# Main_Board.net
KiCad netlist of a schematic drawn in EAGLE
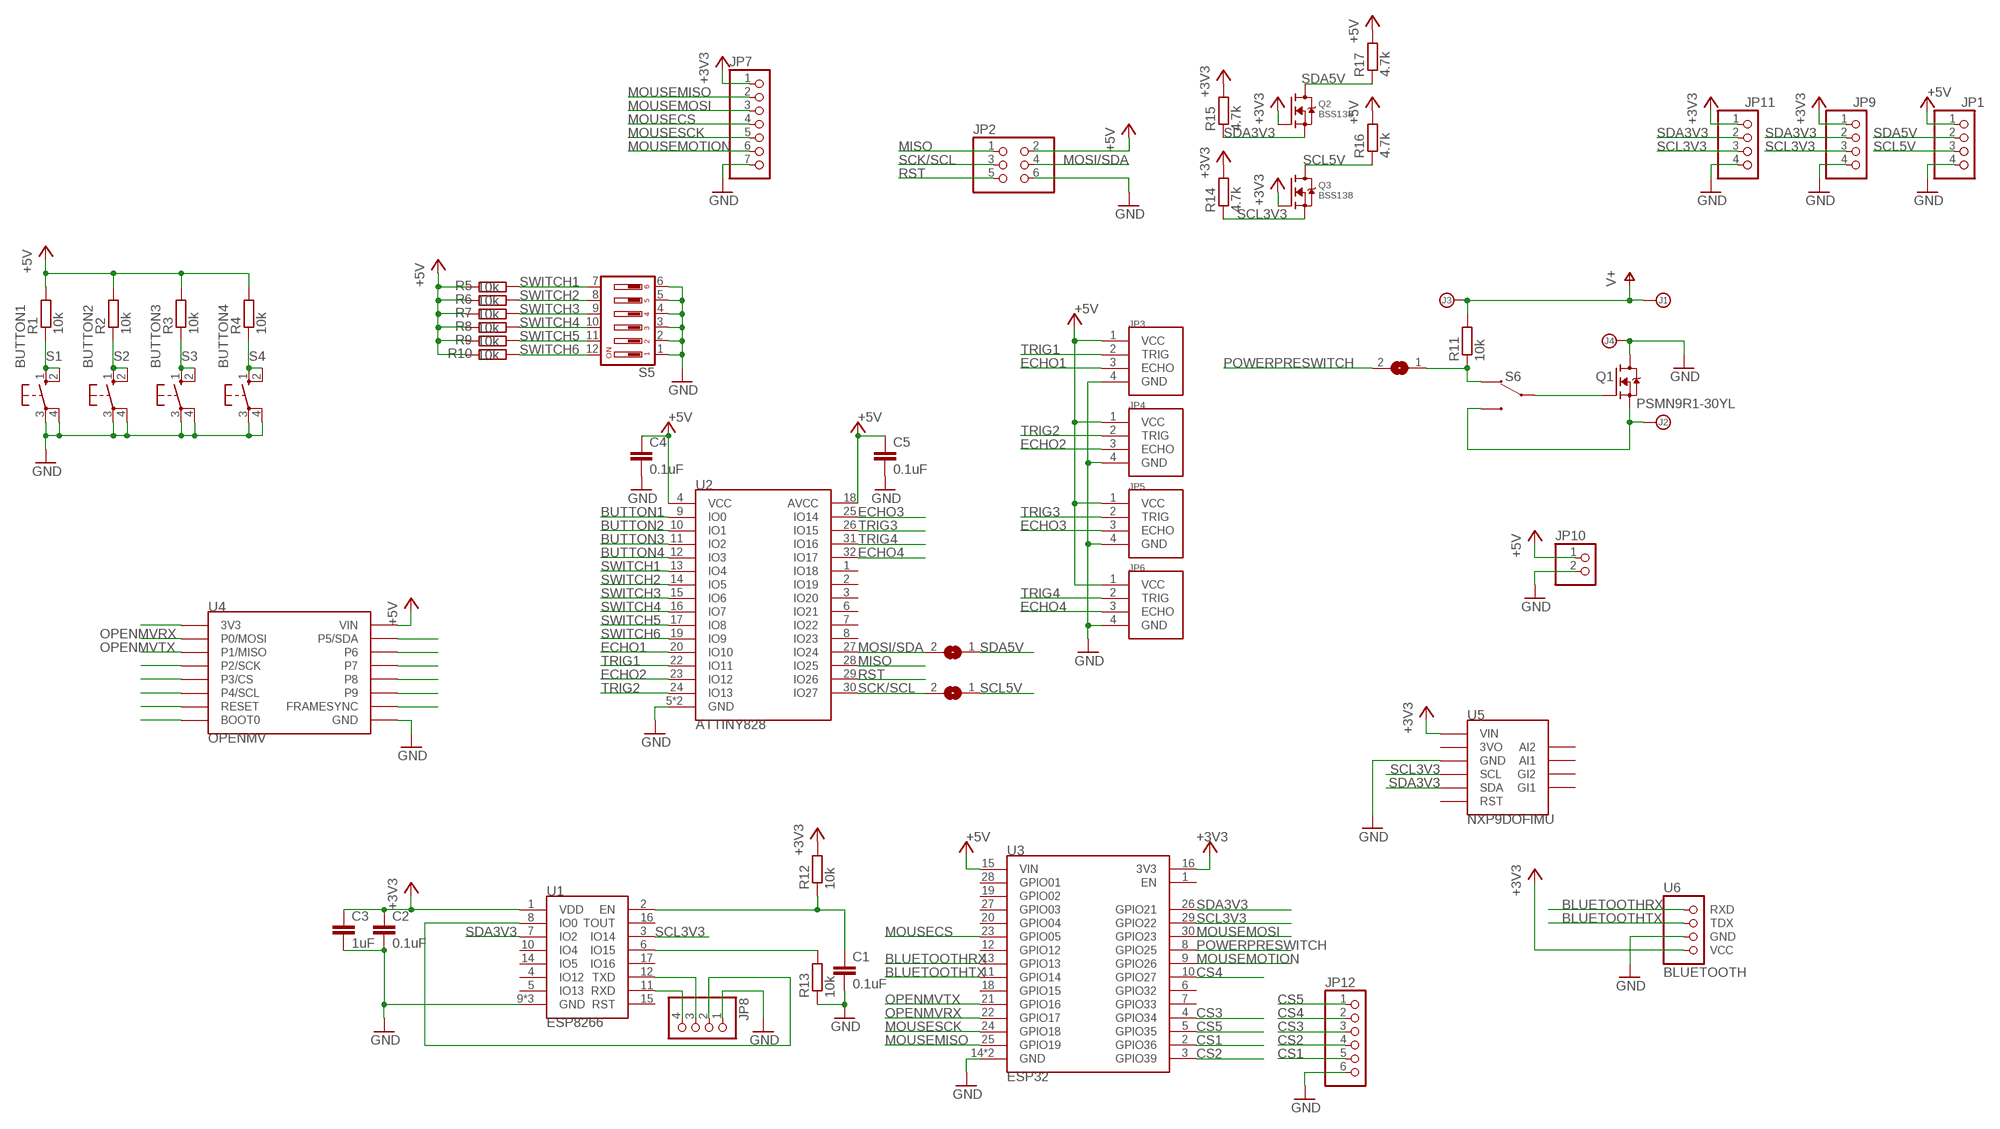
[diagram p0: schematic, sheet 1]

(export (version "E")
  (design (tool "Eeschema 10.0.6"))
  (components
    (comp (ref "C1")
      (value "0.1uF")
      (footprint "eagle-import:C0805")
      (libsource (lib "eagle-import") (part "C-EUC0805"))
    )
    (comp (ref "C2")
      (value "0.1uF")
      (footprint "eagle-import:C0805")
      (libsource (lib "eagle-import") (part "C-EUC0805"))
    )
    (comp (ref "C3")
      (value "1uF")
      (footprint "eagle-import:C0805")
      (libsource (lib "eagle-import") (part "C-EUC0805"))
    )
    (comp (ref "C4")
      (value "0.1uF")
      (footprint "eagle-import:C0805")
      (libsource (lib "eagle-import") (part "C-EUC0805"))
    )
    (comp (ref "C5")
      (value "0.1uF")
      (footprint "eagle-import:C0805")
      (libsource (lib "eagle-import") (part "C-EUC0805"))
    )
    (comp (ref "J1")
      (value "MOLEXQUICKCONNECT")
      (footprint "eagle-import:MOLEXQUICKCONNECT")
      (libsource (lib "eagle-import") (part "MOLEXQUICKCONNECT"))
    )
    (comp (ref "J2")
      (value "MOLEXQUICKCONNECT")
      (footprint "eagle-import:MOLEXQUICKCONNECT")
      (libsource (lib "eagle-import") (part "MOLEXQUICKCONNECT"))
    )
    (comp (ref "J3")
      (value "MOLEXQUICKCONNECT")
      (footprint "eagle-import:MOLEXQUICKCONNECT")
      (libsource (lib "eagle-import") (part "MOLEXQUICKCONNECT"))
    )
    (comp (ref "J4")
      (value "MOLEXQUICKCONNECT")
      (footprint "eagle-import:MOLEXQUICKCONNECT")
      (libsource (lib "eagle-import") (part "MOLEXQUICKCONNECT"))
    )
    (comp (ref "JP1")
      (value "PINHD-1X4")
      (footprint "eagle-import:1X04")
      (libsource (lib "eagle-import") (part "PINHD-1X4"))
    )
    (comp (ref "JP2")
      (value "PINHD-2X3")
      (footprint "eagle-import:2X03")
      (libsource (lib "eagle-import") (part "PINHD-2X3"))
    )
    (comp (ref "JP3")
      (value "HC-SR04")
      (footprint "eagle-import:HC-SR04")
      (libsource (lib "eagle-import") (part "HC-SR04"))
    )
    (comp (ref "JP4")
      (value "HC-SR04")
      (footprint "eagle-import:HC-SR04")
      (libsource (lib "eagle-import") (part "HC-SR04"))
    )
    (comp (ref "JP5")
      (value "HC-SR04")
      (footprint "eagle-import:HC-SR04")
      (libsource (lib "eagle-import") (part "HC-SR04"))
    )
    (comp (ref "JP6")
      (value "HC-SR04")
      (footprint "eagle-import:HC-SR04")
      (libsource (lib "eagle-import") (part "HC-SR04"))
    )
    (comp (ref "JP7")
      (value "PINHD-1X7")
      (footprint "eagle-import:1X07")
      (libsource (lib "eagle-import") (part "PINHD-1X7"))
    )
    (comp (ref "JP8")
      (value "PINHD-1X4")
      (footprint "eagle-import:1X04")
      (libsource (lib "eagle-import") (part "PINHD-1X4"))
    )
    (comp (ref "JP9")
      (value "PINHD-1X4")
      (footprint "eagle-import:1X04")
      (libsource (lib "eagle-import") (part "PINHD-1X4"))
    )
    (comp (ref "JP10")
      (value "PINHD-1X2")
      (footprint "eagle-import:1X02")
      (libsource (lib "eagle-import") (part "PINHD-1X2"))
    )
    (comp (ref "JP11")
      (value "PINHD-1X4")
      (footprint "eagle-import:1X04")
      (libsource (lib "eagle-import") (part "PINHD-1X4"))
    )
    (comp (ref "JP12")
      (value "PINHD-1X6")
      (footprint "eagle-import:1X06")
      (libsource (lib "eagle-import") (part "PINHD-1X6"))
    )
    (comp (ref "Q1")
      (value "PSMN9R1-30YL")
      (footprint "eagle-import:LFPAK")
      (libsource (lib "eagle-import") (part "PSMN9R1-30YL"))
    )
    (comp (ref "Q2")
      (value "BSS138")
      (footprint "eagle-import:SOT95P240X120-3N")
      (fields (field (name "RS_PART_NUMBER") "1241694"))
      (libsource (lib "eagle-import") (part "BSS138"))
    )
    (comp (ref "Q3")
      (value "BSS138")
      (footprint "eagle-import:SOT95P240X120-3N")
      (fields (field (name "RS_PART_NUMBER") "1241694"))
      (libsource (lib "eagle-import") (part "BSS138"))
    )
    (comp (ref "R1")
      (value "10k")
      (footprint "eagle-import:R0805")
      (libsource (lib "eagle-import") (part "R-EU_R0805"))
    )
    (comp (ref "R2")
      (value "10k")
      (footprint "eagle-import:R0805")
      (libsource (lib "eagle-import") (part "R-EU_R0805"))
    )
    (comp (ref "R3")
      (value "10k")
      (footprint "eagle-import:R0805")
      (libsource (lib "eagle-import") (part "R-EU_R0805"))
    )
    (comp (ref "R4")
      (value "10k")
      (footprint "eagle-import:R0805")
      (libsource (lib "eagle-import") (part "R-EU_R0805"))
    )
    (comp (ref "R5")
      (value "10k")
      (footprint "eagle-import:R0805")
      (libsource (lib "eagle-import") (part "R-EU_R0805"))
    )
    (comp (ref "R6")
      (value "10k")
      (footprint "eagle-import:R0805")
      (libsource (lib "eagle-import") (part "R-EU_R0805"))
    )
    (comp (ref "R7")
      (value "10k")
      (footprint "eagle-import:R0805")
      (libsource (lib "eagle-import") (part "R-EU_R0805"))
    )
    (comp (ref "R8")
      (value "10k")
      (footprint "eagle-import:R0805")
      (libsource (lib "eagle-import") (part "R-EU_R0805"))
    )
    (comp (ref "R9")
      (value "10k")
      (footprint "eagle-import:R0805")
      (libsource (lib "eagle-import") (part "R-EU_R0805"))
    )
    (comp (ref "R10")
      (value "10k")
      (footprint "eagle-import:R0805")
      (libsource (lib "eagle-import") (part "R-EU_R0805"))
    )
    (comp (ref "R11")
      (value "10k")
      (footprint "eagle-import:R0805")
      (libsource (lib "eagle-import") (part "R-EU_R0805"))
    )
    (comp (ref "R12")
      (value "10k")
      (footprint "eagle-import:R0805")
      (libsource (lib "eagle-import") (part "R-EU_R0805"))
    )
    (comp (ref "R13")
      (value "10k")
      (footprint "eagle-import:R0805")
      (libsource (lib "eagle-import") (part "R-EU_R0805"))
    )
    (comp (ref "R14")
      (value "4.7k")
      (footprint "eagle-import:R0805")
      (libsource (lib "eagle-import") (part "R-EU_R0805"))
    )
    (comp (ref "R15")
      (value "4.7k")
      (footprint "eagle-import:R0805")
      (libsource (lib "eagle-import") (part "R-EU_R0805"))
    )
    (comp (ref "R16")
      (value "4.7k")
      (footprint "eagle-import:R0805")
      (libsource (lib "eagle-import") (part "R-EU_R0805"))
    )
    (comp (ref "R17")
      (value "4.7k")
      (footprint "eagle-import:R0805")
      (libsource (lib "eagle-import") (part "R-EU_R0805"))
    )
    (comp (ref "S1")
      (value "BUTTON")
      (footprint "eagle-import:BUTTON")
      (fields (field (name "MPN") "B3F-1000"))
      (libsource (lib "eagle-import") (part "BUTTON"))
    )
    (comp (ref "S2")
      (value "BUTTON")
      (footprint "eagle-import:BUTTON")
      (fields (field (name "MPN") "B3F-1000"))
      (libsource (lib "eagle-import") (part "BUTTON"))
    )
    (comp (ref "S3")
      (value "BUTTON")
      (footprint "eagle-import:BUTTON")
      (fields (field (name "MPN") "B3F-1000"))
      (libsource (lib "eagle-import") (part "BUTTON"))
    )
    (comp (ref "S4")
      (value "BUTTON")
      (footprint "eagle-import:BUTTON")
      (fields (field (name "MPN") "B3F-1000"))
      (libsource (lib "eagle-import") (part "BUTTON"))
    )
    (comp (ref "S5")
      (value "SWITCHARRAY6")
      (footprint "eagle-import:SWITCHARRAY6")
      (libsource (lib "eagle-import") (part "SWITCHARRAY6"))
    )
    (comp (ref "S6")
      (value "SS-12D07-VG")
      (footprint "eagle-import:SS-12D07-VG")
      (libsource (lib "eagle-import") (part "SS-12D07-VG"))
    )
    (comp (ref "SJ1") (value "SJ") (footprint "eagle-import:SJ") (libsource (lib "eagle-import") (part "SJ")))
    (comp (ref "SJ2") (value "SJ") (footprint "eagle-import:SJ") (libsource (lib "eagle-import") (part "SJ")))
    (comp (ref "SJ3") (value "SJ") (footprint "eagle-import:SJ") (libsource (lib "eagle-import") (part "SJ")))
    (comp (ref "U1")
      (value "ESP8266")
      (footprint "eagle-import:ESP8266")
      (libsource (lib "eagle-import") (part "ESP8266"))
    )
    (comp (ref "U2")
      (value "ATTINY828")
      (footprint "eagle-import:QFP80P900X900X120-32")
      (libsource (lib "eagle-import") (part "ATTINY828"))
    )
    (comp (ref "U3")
      (value "ESP32")
      (footprint "eagle-import:ESP32")
      (libsource (lib "eagle-import") (part "ESP32"))
    )
    (comp (ref "U4")
      (value "OPENMV")
      (footprint "eagle-import:OPENMV")
      (libsource (lib "eagle-import") (part "OPENMV"))
    )
    (comp (ref "U5")
      (value "NXP9DOFIMU")
      (footprint "eagle-import:NXP9DOFIMU")
      (libsource (lib "eagle-import") (part "NXP9DOFIMU"))
    )
    (comp (ref "U6")
      (value "BLUETOOTH")
      (footprint "eagle-import:BLUETOOTH")
      (libsource (lib "eagle-import") (part "BLUETOOTH"))
    )
  )
  (nets
    (net (code "1") (name "+3V3") (class "Default")
      (node (ref "C2") (pin "1") (pinfunction "1_1") (pintype "passive"))
      (node (ref "C3") (pin "1") (pinfunction "1_1") (pintype "passive"))
      (node (ref "JP11") (pin "1") (pinfunction "1_1") (pintype "passive"))
      (node (ref "JP7") (pin "1") (pinfunction "1_1") (pintype "passive"))
      (node (ref "JP9") (pin "1") (pinfunction "1_1") (pintype "passive"))
      (node (ref "Q2") (pin "1") (pinfunction "G_1") (pintype "bidirectional"))
      (node (ref "Q3") (pin "1") (pinfunction "G_1") (pintype "bidirectional"))
      (node (ref "R12") (pin "2") (pinfunction "2_2") (pintype "passive"))
      (node (ref "R14") (pin "2") (pinfunction "2_2") (pintype "passive"))
      (node (ref "R15") (pin "2") (pinfunction "2_2") (pintype "passive"))
      (node (ref "U1") (pin "1") (pinfunction "VDD_1") (pintype "power_in"))
      (node (ref "U3") (pin "16") (pinfunction "3V3_16") (pintype "bidirectional"))
      (node (ref "U5") (pin "VIN") (pinfunction "VIN_VIN") (pintype "power_in"))
      (node (ref "U6") (pin "VCC") (pinfunction "VCC_VCC") (pintype "passive"))
    )
    (net (code "2") (name "+5V") (class "Default")
      (node (ref "C4") (pin "1") (pinfunction "1_1") (pintype "passive"))
      (node (ref "C5") (pin "1") (pinfunction "1_1") (pintype "passive"))
      (node (ref "JP1") (pin "1") (pinfunction "1_1") (pintype "passive"))
      (node (ref "JP10") (pin "1") (pinfunction "1_1") (pintype "passive"))
      (node (ref "JP2") (pin "2") (pinfunction "2_2") (pintype "passive"))
      (node (ref "JP3") (pin "1") (pinfunction "VCC_1") (pintype "bidirectional"))
      (node (ref "JP4") (pin "1") (pinfunction "VCC_1") (pintype "bidirectional"))
      (node (ref "JP5") (pin "1") (pinfunction "VCC_1") (pintype "bidirectional"))
      (node (ref "JP6") (pin "1") (pinfunction "VCC_1") (pintype "bidirectional"))
      (node (ref "R1") (pin "2") (pinfunction "2_2") (pintype "passive"))
      (node (ref "R10") (pin "2") (pinfunction "2_2") (pintype "passive"))
      (node (ref "R16") (pin "2") (pinfunction "2_2") (pintype "passive"))
      (node (ref "R17") (pin "2") (pinfunction "2_2") (pintype "passive"))
      (node (ref "R2") (pin "2") (pinfunction "2_2") (pintype "passive"))
      (node (ref "R3") (pin "2") (pinfunction "2_2") (pintype "passive"))
      (node (ref "R4") (pin "2") (pinfunction "2_2") (pintype "passive"))
      (node (ref "R5") (pin "2") (pinfunction "2_2") (pintype "passive"))
      (node (ref "R6") (pin "2") (pinfunction "2_2") (pintype "passive"))
      (node (ref "R7") (pin "2") (pinfunction "2_2") (pintype "passive"))
      (node (ref "R8") (pin "2") (pinfunction "2_2") (pintype "passive"))
      (node (ref "R9") (pin "2") (pinfunction "2_2") (pintype "passive"))
      (node (ref "U2") (pin "18") (pinfunction "AVCC_18") (pintype "power_in"))
      (node (ref "U2") (pin "4") (pinfunction "VCC_4") (pintype "power_in"))
      (node (ref "U3") (pin "15") (pinfunction "VIN_15") (pintype "bidirectional"))
      (node (ref "U4") (pin "15") (pinfunction "VIN_15") (pintype "power_in"))
      (node (ref "U4") (pin "15ALT") (pinfunction "VIN_15ALT") (pintype "power_in"))
      (node (ref "U4") (pin "P$15") (pinfunction "VIN_P$15") (pintype "power_in"))
    )
    (net (code "3") (name "/3VO") (class "Default")
      (node (ref "U5") (pin "3VO") (pinfunction "3VO_3VO") (pintype "power_in"))
    )
    (net (code "4") (name "/BLUETOOTHRX") (class "Default")
      (node (ref "U3") (pin "13") (pinfunction "GPIO13_13") (pintype "bidirectional"))
      (node (ref "U6") (pin "RXD") (pinfunction "RXD_RXD") (pintype "passive"))
    )
    (net (code "5") (name "/BLUETOOTHTX") (class "Default")
      (node (ref "U3") (pin "11") (pinfunction "GPIO14_11") (pintype "bidirectional"))
      (node (ref "U6") (pin "TXD") (pinfunction "TDX_TXD") (pintype "passive"))
    )
    (net (code "6") (name "/BUTTON1") (class "Default")
      (node (ref "R1") (pin "1") (pinfunction "1_1") (pintype "passive"))
      (node (ref "S1") (pin "1") (pinfunction "S_1") (pintype "passive"))
      (node (ref "S1") (pin "2") (pinfunction "S1_2") (pintype "passive"))
      (node (ref "U2") (pin "9") (pinfunction "IO0_9") (pintype "bidirectional"))
    )
    (net (code "7") (name "/BUTTON2") (class "Default")
      (node (ref "R2") (pin "1") (pinfunction "1_1") (pintype "passive"))
      (node (ref "S2") (pin "1") (pinfunction "S_1") (pintype "passive"))
      (node (ref "S2") (pin "2") (pinfunction "S1_2") (pintype "passive"))
      (node (ref "U2") (pin "10") (pinfunction "IO1_10") (pintype "bidirectional"))
    )
    (net (code "8") (name "/BUTTON3") (class "Default")
      (node (ref "R3") (pin "1") (pinfunction "1_1") (pintype "passive"))
      (node (ref "S3") (pin "1") (pinfunction "S_1") (pintype "passive"))
      (node (ref "S3") (pin "2") (pinfunction "S1_2") (pintype "passive"))
      (node (ref "U2") (pin "11") (pinfunction "IO2_11") (pintype "bidirectional"))
    )
    (net (code "9") (name "/BUTTON4") (class "Default")
      (node (ref "R4") (pin "1") (pinfunction "1_1") (pintype "passive"))
      (node (ref "S4") (pin "1") (pinfunction "S_1") (pintype "passive"))
      (node (ref "S4") (pin "2") (pinfunction "S1_2") (pintype "passive"))
      (node (ref "U2") (pin "12") (pinfunction "IO3_12") (pintype "bidirectional"))
    )
    (net (code "10") (name "/CS1") (class "Default")
      (node (ref "JP12") (pin "5") (pinfunction "5_5") (pintype "passive"))
      (node (ref "U3") (pin "2") (pinfunction "GPIO36_2") (pintype "bidirectional"))
    )
    (net (code "11") (name "/CS2") (class "Default")
      (node (ref "JP12") (pin "4") (pinfunction "4_4") (pintype "passive"))
      (node (ref "U3") (pin "3") (pinfunction "GPIO39_3") (pintype "bidirectional"))
    )
    (net (code "12") (name "/CS3") (class "Default")
      (node (ref "JP12") (pin "3") (pinfunction "3_3") (pintype "passive"))
      (node (ref "U3") (pin "4") (pinfunction "GPIO34_4") (pintype "bidirectional"))
    )
    (net (code "13") (name "/CS4") (class "Default")
      (node (ref "JP12") (pin "2") (pinfunction "2_2") (pintype "passive"))
      (node (ref "U3") (pin "10") (pinfunction "GPIO27_10") (pintype "bidirectional"))
    )
    (net (code "14") (name "/CS5") (class "Default")
      (node (ref "JP12") (pin "1") (pinfunction "1_1") (pintype "passive"))
      (node (ref "U3") (pin "5") (pinfunction "GPIO35_5") (pintype "bidirectional"))
    )
    (net (code "15") (name "/ECHO1") (class "Default")
      (node (ref "JP3") (pin "3") (pinfunction "ECHO_3") (pintype "bidirectional"))
      (node (ref "U2") (pin "20") (pinfunction "IO10_20") (pintype "bidirectional"))
    )
    (net (code "16") (name "/ECHO2") (class "Default")
      (node (ref "JP4") (pin "3") (pinfunction "ECHO_3") (pintype "bidirectional"))
      (node (ref "U2") (pin "23") (pinfunction "IO12_23") (pintype "bidirectional"))
    )
    (net (code "17") (name "/ECHO3") (class "Default")
      (node (ref "JP5") (pin "3") (pinfunction "ECHO_3") (pintype "bidirectional"))
      (node (ref "U2") (pin "25") (pinfunction "IO14_25") (pintype "bidirectional"))
    )
    (net (code "18") (name "/ECHO4") (class "Default")
      (node (ref "JP6") (pin "3") (pinfunction "ECHO_3") (pintype "bidirectional"))
      (node (ref "U2") (pin "32") (pinfunction "IO17_32") (pintype "bidirectional"))
    )
    (net (code "19") (name "/MISO") (class "Default")
      (node (ref "JP2") (pin "1") (pinfunction "1_1") (pintype "passive"))
      (node (ref "U2") (pin "28") (pinfunction "IO25_28") (pintype "bidirectional"))
    )
    (net (code "20") (name "/MOSI{slash}SDA") (class "Default")
      (node (ref "JP2") (pin "4") (pinfunction "4_4") (pintype "passive"))
      (node (ref "SJ2") (pin "2") (pinfunction "2_2") (pintype "passive"))
      (node (ref "U2") (pin "27") (pinfunction "IO24_27") (pintype "bidirectional"))
    )
    (net (code "21") (name "/MOUSECS") (class "Default")
      (node (ref "JP7") (pin "4") (pinfunction "4_4") (pintype "passive"))
      (node (ref "U3") (pin "23") (pinfunction "GPIO05_23") (pintype "bidirectional"))
    )
    (net (code "22") (name "/MOUSEMISO") (class "Default")
      (node (ref "JP7") (pin "2") (pinfunction "2_2") (pintype "passive"))
      (node (ref "U3") (pin "25") (pinfunction "GPIO19_25") (pintype "bidirectional"))
    )
    (net (code "23") (name "/MOUSEMOSI") (class "Default")
      (node (ref "JP7") (pin "3") (pinfunction "3_3") (pintype "passive"))
      (node (ref "U3") (pin "30") (pinfunction "GPIO23_30") (pintype "bidirectional"))
    )
    (net (code "24") (name "/MOUSEMOTION") (class "Default")
      (node (ref "JP7") (pin "6") (pinfunction "6_6") (pintype "passive"))
      (node (ref "U3") (pin "9") (pinfunction "GPIO26_9") (pintype "bidirectional"))
    )
    (net (code "25") (name "/MOUSESCK") (class "Default")
      (node (ref "JP7") (pin "5") (pinfunction "5_5") (pintype "passive"))
      (node (ref "U3") (pin "24") (pinfunction "GPIO18_24") (pintype "bidirectional"))
    )
    (net (code "26") (name "/OPENMVRX") (class "Default")
      (node (ref "U3") (pin "22") (pinfunction "GPIO17_22") (pintype "bidirectional"))
      (node (ref "U4") (pin "1") (pinfunction "P0/MOSI_1") (pintype "bidirectional"))
      (node (ref "U4") (pin "1ALT") (pinfunction "P0/MOSI_1ALT") (pintype "bidirectional"))
      (node (ref "U4") (pin "P$1") (pinfunction "P0/MOSI_P$1") (pintype "bidirectional"))
    )
    (net (code "27") (name "/OPENMVTX") (class "Default")
      (node (ref "U3") (pin "21") (pinfunction "GPIO16_21") (pintype "bidirectional"))
      (node (ref "U4") (pin "2") (pinfunction "P1/MISO_2") (pintype "bidirectional"))
      (node (ref "U4") (pin "2ALT") (pinfunction "P1/MISO_2ALT") (pintype "bidirectional"))
      (node (ref "U4") (pin "P$2") (pinfunction "P1/MISO_P$2") (pintype "bidirectional"))
    )
    (net (code "28") (name "/POWERPRESWITCH") (class "Default")
      (node (ref "SJ1") (pin "2") (pinfunction "2_2") (pintype "passive"))
      (node (ref "U3") (pin "8") (pinfunction "GPIO25_8") (pintype "bidirectional"))
    )
    (net (code "29") (name "/RST") (class "Default")
      (node (ref "JP2") (pin "5") (pinfunction "5_5") (pintype "passive"))
      (node (ref "U2") (pin "29") (pinfunction "IO26_29") (pintype "bidirectional"))
    )
    (net (code "30") (name "/SCK{slash}SCL") (class "Default")
      (node (ref "JP2") (pin "3") (pinfunction "3_3") (pintype "passive"))
      (node (ref "SJ3") (pin "2") (pinfunction "2_2") (pintype "passive"))
      (node (ref "U2") (pin "30") (pinfunction "IO27_30") (pintype "bidirectional"))
    )
    (net (code "31") (name "/SCL3V3") (class "Default")
      (node (ref "JP11") (pin "3") (pinfunction "3_3") (pintype "passive"))
      (node (ref "JP9") (pin "3") (pinfunction "3_3") (pintype "passive"))
      (node (ref "Q3") (pin "2") (pinfunction "S_2") (pintype "bidirectional"))
      (node (ref "R14") (pin "1") (pinfunction "1_1") (pintype "passive"))
      (node (ref "U1") (pin "3") (pinfunction "IO14_3") (pintype "bidirectional"))
      (node (ref "U3") (pin "29") (pinfunction "GPIO22_29") (pintype "bidirectional"))
      (node (ref "U5") (pin "SCL") (pinfunction "SCL_SCL") (pintype "bidirectional"))
    )
    (net (code "32") (name "/SCL5V") (class "Default")
      (node (ref "JP1") (pin "3") (pinfunction "3_3") (pintype "passive"))
      (node (ref "Q3") (pin "3") (pinfunction "D_3") (pintype "bidirectional"))
      (node (ref "R16") (pin "1") (pinfunction "1_1") (pintype "passive"))
      (node (ref "SJ3") (pin "1") (pinfunction "1_1") (pintype "passive"))
    )
    (net (code "33") (name "/SDA3V3") (class "Default")
      (node (ref "JP11") (pin "2") (pinfunction "2_2") (pintype "passive"))
      (node (ref "JP9") (pin "2") (pinfunction "2_2") (pintype "passive"))
      (node (ref "Q2") (pin "2") (pinfunction "S_2") (pintype "bidirectional"))
      (node (ref "R15") (pin "1") (pinfunction "1_1") (pintype "passive"))
      (node (ref "U1") (pin "7") (pinfunction "IO2_7") (pintype "bidirectional"))
      (node (ref "U3") (pin "26") (pinfunction "GPIO21_26") (pintype "bidirectional"))
      (node (ref "U5") (pin "SDA") (pinfunction "SDA_SDA") (pintype "bidirectional"))
    )
    (net (code "34") (name "/SDA5V") (class "Default")
      (node (ref "JP1") (pin "2") (pinfunction "2_2") (pintype "passive"))
      (node (ref "Q2") (pin "3") (pinfunction "D_3") (pintype "bidirectional"))
      (node (ref "R17") (pin "1") (pinfunction "1_1") (pintype "passive"))
      (node (ref "SJ2") (pin "1") (pinfunction "1_1") (pintype "passive"))
    )
    (net (code "35") (name "/SWITCH1") (class "Default")
      (node (ref "R5") (pin "1") (pinfunction "1_1") (pintype "passive"))
      (node (ref "S5") (pin "7") (pinfunction "7_7") (pintype "passive"))
      (node (ref "U2") (pin "13") (pinfunction "IO4_13") (pintype "bidirectional"))
    )
    (net (code "36") (name "/SWITCH2") (class "Default")
      (node (ref "R6") (pin "1") (pinfunction "1_1") (pintype "passive"))
      (node (ref "S5") (pin "8") (pinfunction "8_8") (pintype "passive"))
      (node (ref "U2") (pin "14") (pinfunction "IO5_14") (pintype "bidirectional"))
    )
    (net (code "37") (name "/SWITCH3") (class "Default")
      (node (ref "R7") (pin "1") (pinfunction "1_1") (pintype "passive"))
      (node (ref "S5") (pin "9") (pinfunction "9_9") (pintype "passive"))
      (node (ref "U2") (pin "15") (pinfunction "IO6_15") (pintype "bidirectional"))
    )
    (net (code "38") (name "/SWITCH4") (class "Default")
      (node (ref "R8") (pin "1") (pinfunction "1_1") (pintype "passive"))
      (node (ref "S5") (pin "10") (pinfunction "10_10") (pintype "passive"))
      (node (ref "U2") (pin "16") (pinfunction "IO7_16") (pintype "bidirectional"))
    )
    (net (code "39") (name "/SWITCH5") (class "Default")
      (node (ref "R9") (pin "1") (pinfunction "1_1") (pintype "passive"))
      (node (ref "S5") (pin "11") (pinfunction "11_11") (pintype "passive"))
      (node (ref "U2") (pin "17") (pinfunction "IO8_17") (pintype "bidirectional"))
    )
    (net (code "40") (name "/SWITCH6") (class "Default")
      (node (ref "R10") (pin "1") (pinfunction "1_1") (pintype "passive"))
      (node (ref "S5") (pin "12") (pinfunction "12_12") (pintype "passive"))
      (node (ref "U2") (pin "19") (pinfunction "IO9_19") (pintype "bidirectional"))
    )
    (net (code "41") (name "/TRIG1") (class "Default")
      (node (ref "JP3") (pin "2") (pinfunction "TRIG_2") (pintype "bidirectional"))
      (node (ref "U2") (pin "22") (pinfunction "IO11_22") (pintype "bidirectional"))
    )
    (net (code "42") (name "/TRIG2") (class "Default")
      (node (ref "JP4") (pin "2") (pinfunction "TRIG_2") (pintype "bidirectional"))
      (node (ref "U2") (pin "24") (pinfunction "IO13_24") (pintype "bidirectional"))
    )
    (net (code "43") (name "/TRIG3") (class "Default")
      (node (ref "JP5") (pin "2") (pinfunction "TRIG_2") (pintype "bidirectional"))
      (node (ref "U2") (pin "26") (pinfunction "IO15_26") (pintype "bidirectional"))
    )
    (net (code "44") (name "/TRIG4") (class "Default")
      (node (ref "JP6") (pin "2") (pinfunction "TRIG_2") (pintype "bidirectional"))
      (node (ref "U2") (pin "31") (pinfunction "IO16_31") (pintype "bidirectional"))
    )
    (net (code "45") (name "GND") (class "Default")
      (node (ref "C1") (pin "2") (pinfunction "2_2") (pintype "passive"))
      (node (ref "C2") (pin "2") (pinfunction "2_2") (pintype "passive"))
      (node (ref "C3") (pin "2") (pinfunction "2_2") (pintype "passive"))
      (node (ref "C4") (pin "2") (pinfunction "2_2") (pintype "passive"))
      (node (ref "C5") (pin "2") (pinfunction "2_2") (pintype "passive"))
      (node (ref "J4") (pin "P$1") (pinfunction "1_P$1") (pintype "passive"))
      (node (ref "J4") (pin "P$3") (pinfunction "1_P$3") (pintype "passive"))
      (node (ref "J4") (pin "P$4") (pinfunction "1_P$4") (pintype "passive"))
      (node (ref "JP1") (pin "4") (pinfunction "4_4") (pintype "passive"))
      (node (ref "JP10") (pin "2") (pinfunction "2_2") (pintype "passive"))
      (node (ref "JP11") (pin "4") (pinfunction "4_4") (pintype "passive"))
      (node (ref "JP12") (pin "6") (pinfunction "6_6") (pintype "passive"))
      (node (ref "JP2") (pin "6") (pinfunction "6_6") (pintype "passive"))
      (node (ref "JP3") (pin "4") (pinfunction "GND_4") (pintype "bidirectional"))
      (node (ref "JP4") (pin "4") (pinfunction "GND_4") (pintype "bidirectional"))
      (node (ref "JP5") (pin "4") (pinfunction "GND_4") (pintype "bidirectional"))
      (node (ref "JP6") (pin "4") (pinfunction "GND_4") (pintype "bidirectional"))
      (node (ref "JP7") (pin "7") (pinfunction "7_7") (pintype "passive"))
      (node (ref "JP8") (pin "1") (pinfunction "1_1") (pintype "passive"))
      (node (ref "JP9") (pin "4") (pinfunction "4_4") (pintype "passive"))
      (node (ref "Q1") (pin "TAB") (pinfunction "D_TAB") (pintype "passive"))
      (node (ref "R13") (pin "1") (pinfunction "1_1") (pintype "passive"))
      (node (ref "S1") (pin "3") (pinfunction "P_3") (pintype "passive"))
      (node (ref "S1") (pin "4") (pinfunction "P1_4") (pintype "passive"))
      (node (ref "S2") (pin "3") (pinfunction "P_3") (pintype "passive"))
      (node (ref "S2") (pin "4") (pinfunction "P1_4") (pintype "passive"))
      (node (ref "S3") (pin "3") (pinfunction "P_3") (pintype "passive"))
      (node (ref "S3") (pin "4") (pinfunction "P1_4") (pintype "passive"))
      (node (ref "S4") (pin "3") (pinfunction "P_3") (pintype "passive"))
      (node (ref "S4") (pin "4") (pinfunction "P1_4") (pintype "passive"))
      (node (ref "S5") (pin "1") (pinfunction "1_1") (pintype "passive"))
      (node (ref "S5") (pin "2") (pinfunction "2_2") (pintype "passive"))
      (node (ref "S5") (pin "3") (pinfunction "3_3") (pintype "passive"))
      (node (ref "S5") (pin "4") (pinfunction "4_4") (pintype "passive"))
      (node (ref "S5") (pin "5") (pinfunction "5_5") (pintype "passive"))
      (node (ref "S5") (pin "6") (pinfunction "6_6") (pintype "passive"))
      (node (ref "U1") (pin "13") (pinfunction "GND_13") (pintype "power_in"))
      (node (ref "U1") (pin "18") (pinfunction "GND_18") (pintype "power_in"))
      (node (ref "U1") (pin "9") (pinfunction "GND_9") (pintype "power_in"))
      (node (ref "U2") (pin "21") (pinfunction "GND_21") (pintype "power_in"))
      (node (ref "U2") (pin "5") (pinfunction "GND_5") (pintype "power_in"))
      (node (ref "U3") (pin "14") (pinfunction "GND_14") (pintype "bidirectional"))
      (node (ref "U3") (pin "17") (pinfunction "GND_17") (pintype "bidirectional"))
      (node (ref "U4") (pin "16") (pinfunction "GND_16") (pintype "power_in"))
      (node (ref "U4") (pin "16ALT") (pinfunction "GND_16ALT") (pintype "power_in"))
      (node (ref "U4") (pin "P$16") (pinfunction "GND_P$16") (pintype "power_in"))
      (node (ref "U5") (pin "GND") (pinfunction "GND_GND") (pintype "power_in"))
      (node (ref "U6") (pin "GND") (pinfunction "GND_GND") (pintype "passive"))
    )
    (net (code "46") (name "Net-(J2-1-PadP$1)") (class "Default")
      (node (ref "J2") (pin "P$1") (pinfunction "1_P$1") (pintype "passive"))
      (node (ref "J2") (pin "P$3") (pinfunction "1_P$3") (pintype "passive"))
      (node (ref "J2") (pin "P$4") (pinfunction "1_P$4") (pintype "passive"))
      (node (ref "Q1") (pin "1") (pinfunction "S_1") (pintype "passive"))
      (node (ref "Q1") (pin "2") (pinfunction "S_2") (pintype "passive"))
      (node (ref "Q1") (pin "3") (pinfunction "S_3") (pintype "passive"))
      (node (ref "S6") (pin "2") (pinfunction "2_2") (pintype "passive"))
    )
    (net (code "47") (name "Net-(Q1-G)") (class "Default")
      (node (ref "Q1") (pin "4") (pinfunction "G_4") (pintype "passive"))
      (node (ref "S6") (pin "COM") (pinfunction "COM_COM") (pintype "passive"))
    )
    (net (code "48") (name "Net-(R11-Pad1)") (class "Default")
      (node (ref "R11") (pin "1") (pinfunction "1_1") (pintype "passive"))
      (node (ref "S6") (pin "1") (pinfunction "1_1") (pintype "passive"))
      (node (ref "SJ1") (pin "1") (pinfunction "1_1") (pintype "passive"))
    )
    (net (code "49") (name "Net-(U1-EN)") (class "Default")
      (node (ref "C1") (pin "1") (pinfunction "1_1") (pintype "passive"))
      (node (ref "R12") (pin "1") (pinfunction "1_1") (pintype "passive"))
      (node (ref "U1") (pin "2") (pinfunction "EN_2") (pintype "bidirectional"))
    )
    (net (code "50") (name "Net-(U1-IO0)") (class "Default")
      (node (ref "JP8") (pin "2") (pinfunction "2_2") (pintype "passive"))
      (node (ref "U1") (pin "8") (pinfunction "IO0_8") (pintype "bidirectional"))
    )
    (net (code "51") (name "Net-(U1-IO15)") (class "Default")
      (node (ref "R13") (pin "2") (pinfunction "2_2") (pintype "passive"))
      (node (ref "U1") (pin "6") (pinfunction "IO15_6") (pintype "bidirectional"))
    )
    (net (code "52") (name "Net-(U1-RXD)") (class "Default")
      (node (ref "JP8") (pin "4") (pinfunction "4_4") (pintype "passive"))
      (node (ref "U1") (pin "11") (pinfunction "RXD_11") (pintype "bidirectional"))
    )
    (net (code "53") (name "Net-(U1-TXD)") (class "Default")
      (node (ref "JP8") (pin "3") (pinfunction "3_3") (pintype "passive"))
      (node (ref "U1") (pin "12") (pinfunction "TXD_12") (pintype "bidirectional"))
    )
    (net (code "54") (name "Net-(U4-3V3-Pad8)") (class "Default")
      (node (ref "U4") (pin "8") (pinfunction "3V3_8") (pintype "power_in"))
      (node (ref "U4") (pin "8ALT") (pinfunction "3V3_8ALT") (pintype "power_in"))
      (node (ref "U4") (pin "P$8") (pinfunction "3V3_P$8") (pintype "power_in"))
    )
    (net (code "55") (name "Net-(U4-BOOT0-Pad10)") (class "Default")
      (node (ref "U4") (pin "10") (pinfunction "BOOT0_10") (pintype "bidirectional"))
      (node (ref "U4") (pin "10ALT") (pinfunction "BOOT0_10ALT") (pintype "bidirectional"))
      (node (ref "U4") (pin "P$10") (pinfunction "BOOT0_P$10") (pintype "bidirectional"))
    )
    (net (code "56") (name "Net-(U4-FRAMESYNC-Pad11)") (class "Default")
      (node (ref "U4") (pin "11") (pinfunction "FRAMESYNC_11") (pintype "bidirectional"))
      (node (ref "U4") (pin "11ALT") (pinfunction "FRAMESYNC_11ALT") (pintype "bidirectional"))
      (node (ref "U4") (pin "P$11") (pinfunction "FRAMESYNC_P$11") (pintype "bidirectional"))
    )
    (net (code "57") (name "Net-(U4-P2{slash}SCK-Pad3)") (class "Default")
      (node (ref "U4") (pin "3") (pinfunction "P2/SCK_3") (pintype "bidirectional"))
      (node (ref "U4") (pin "3ALT") (pinfunction "P2/SCK_3ALT") (pintype "bidirectional"))
      (node (ref "U4") (pin "P$3") (pinfunction "P2/SCK_P$3") (pintype "bidirectional"))
    )
    (net (code "58") (name "Net-(U4-P3{slash}CS-Pad4)") (class "Default")
      (node (ref "U4") (pin "4") (pinfunction "P3/CS_4") (pintype "bidirectional"))
      (node (ref "U4") (pin "4ALT") (pinfunction "P3/CS_4ALT") (pintype "bidirectional"))
      (node (ref "U4") (pin "P$4") (pinfunction "P3/CS_P$4") (pintype "bidirectional"))
    )
    (net (code "59") (name "Net-(U4-P4{slash}SCL-Pad5)") (class "Default")
      (node (ref "U4") (pin "5") (pinfunction "P4/SCL_5") (pintype "bidirectional"))
      (node (ref "U4") (pin "5ALT") (pinfunction "P4/SCL_5ALT") (pintype "bidirectional"))
      (node (ref "U4") (pin "P$5") (pinfunction "P4/SCL_P$5") (pintype "bidirectional"))
    )
    (net (code "60") (name "Net-(U4-P5{slash}SDA-Pad6)") (class "Default")
      (node (ref "U4") (pin "6") (pinfunction "P5/SDA_6") (pintype "bidirectional"))
      (node (ref "U4") (pin "6ALT") (pinfunction "P5/SDA_6ALT") (pintype "bidirectional"))
      (node (ref "U4") (pin "P$6") (pinfunction "P5/SDA_P$6") (pintype "bidirectional"))
    )
    (net (code "61") (name "Net-(U4-P6-Pad7)") (class "Default")
      (node (ref "U4") (pin "7") (pinfunction "P6_7") (pintype "bidirectional"))
      (node (ref "U4") (pin "7ALT") (pinfunction "P6_7ALT") (pintype "bidirectional"))
      (node (ref "U4") (pin "P$7") (pinfunction "P6_P$7") (pintype "bidirectional"))
    )
    (net (code "62") (name "Net-(U4-P7-Pad14)") (class "Default")
      (node (ref "U4") (pin "14") (pinfunction "P7_14") (pintype "bidirectional"))
      (node (ref "U4") (pin "14ALT") (pinfunction "P7_14ALT") (pintype "bidirectional"))
      (node (ref "U4") (pin "P$14") (pinfunction "P7_P$14") (pintype "bidirectional"))
    )
    (net (code "63") (name "Net-(U4-P8-Pad13)") (class "Default")
      (node (ref "U4") (pin "13") (pinfunction "P8_13") (pintype "bidirectional"))
      (node (ref "U4") (pin "13ALT") (pinfunction "P8_13ALT") (pintype "bidirectional"))
      (node (ref "U4") (pin "P$13") (pinfunction "P8_P$13") (pintype "bidirectional"))
    )
    (net (code "64") (name "Net-(U4-P9-Pad12)") (class "Default")
      (node (ref "U4") (pin "12") (pinfunction "P9_12") (pintype "bidirectional"))
      (node (ref "U4") (pin "12ALT") (pinfunction "P9_12ALT") (pintype "bidirectional"))
      (node (ref "U4") (pin "P$12") (pinfunction "P9_P$12") (pintype "bidirectional"))
    )
    (net (code "65") (name "Net-(U4-RESET-Pad9)") (class "Default")
      (node (ref "U4") (pin "9") (pinfunction "RESET_9") (pintype "bidirectional"))
      (node (ref "U4") (pin "9ALT") (pinfunction "RESET_9ALT") (pintype "bidirectional"))
      (node (ref "U4") (pin "P$9") (pinfunction "RESET_P$9") (pintype "bidirectional"))
    )
    (net (code "66") (name "V+") (class "Default")
      (node (ref "J1") (pin "P$1") (pinfunction "1_P$1") (pintype "passive"))
      (node (ref "J1") (pin "P$3") (pinfunction "1_P$3") (pintype "passive"))
      (node (ref "J1") (pin "P$4") (pinfunction "1_P$4") (pintype "passive"))
      (node (ref "J3") (pin "P$1") (pinfunction "1_P$1") (pintype "passive"))
      (node (ref "J3") (pin "P$3") (pinfunction "1_P$3") (pintype "passive"))
      (node (ref "J3") (pin "P$4") (pinfunction "1_P$4") (pintype "passive"))
      (node (ref "R11") (pin "2") (pinfunction "2_2") (pintype "passive"))
    )
    (net (code "67") (name "unconnected-(U1-IO4-Pad10)") (class "Default")
      (node (ref "U1") (pin "10") (pinfunction "IO4_10") (pintype "bidirectional"))
    )
    (net (code "68") (name "unconnected-(U1-IO5-Pad14)") (class "Default")
      (node (ref "U1") (pin "14") (pinfunction "IO5_14") (pintype "bidirectional"))
    )
    (net (code "69") (name "unconnected-(U1-IO12-Pad4)") (class "Default")
      (node (ref "U1") (pin "4") (pinfunction "IO12_4") (pintype "bidirectional"))
    )
    (net (code "70") (name "unconnected-(U1-IO13-Pad5)") (class "Default")
      (node (ref "U1") (pin "5") (pinfunction "IO13_5") (pintype "bidirectional"))
    )
    (net (code "71") (name "unconnected-(U1-IO16-Pad17)") (class "Default")
      (node (ref "U1") (pin "17") (pinfunction "IO16_17") (pintype "bidirectional"))
    )
    (net (code "72") (name "unconnected-(U1-RST-Pad15)") (class "Default")
      (node (ref "U1") (pin "15") (pinfunction "RST_15") (pintype "bidirectional"))
    )
    (net (code "73") (name "unconnected-(U1-TOUT-Pad16)") (class "Default")
      (node (ref "U1") (pin "16") (pinfunction "TOUT_16") (pintype "bidirectional"))
    )
    (net (code "74") (name "unconnected-(U2-IO18-Pad1)") (class "Default")
      (node (ref "U2") (pin "1") (pinfunction "IO18_1") (pintype "bidirectional"))
    )
    (net (code "75") (name "unconnected-(U2-IO19-Pad2)") (class "Default")
      (node (ref "U2") (pin "2") (pinfunction "IO19_2") (pintype "bidirectional"))
    )
    (net (code "76") (name "unconnected-(U2-IO20-Pad3)") (class "Default")
      (node (ref "U2") (pin "3") (pinfunction "IO20_3") (pintype "bidirectional"))
    )
    (net (code "77") (name "unconnected-(U2-IO21-Pad6)") (class "Default")
      (node (ref "U2") (pin "6") (pinfunction "IO21_6") (pintype "bidirectional"))
    )
    (net (code "78") (name "unconnected-(U2-IO22-Pad7)") (class "Default")
      (node (ref "U2") (pin "7") (pinfunction "IO22_7") (pintype "bidirectional"))
    )
    (net (code "79") (name "unconnected-(U2-IO23-Pad8)") (class "Default")
      (node (ref "U2") (pin "8") (pinfunction "IO23_8") (pintype "bidirectional"))
    )
    (net (code "80") (name "unconnected-(U3-EN-Pad1)") (class "Default")
      (node (ref "U3") (pin "1") (pinfunction "EN_1") (pintype "bidirectional"))
    )
    (net (code "81") (name "unconnected-(U3-GPIO01-Pad28)") (class "Default")
      (node (ref "U3") (pin "28") (pinfunction "GPIO01_28") (pintype "bidirectional"))
    )
    (net (code "82") (name "unconnected-(U3-GPIO02-Pad19)") (class "Default")
      (node (ref "U3") (pin "19") (pinfunction "GPIO02_19") (pintype "bidirectional"))
    )
    (net (code "83") (name "unconnected-(U3-GPIO03-Pad27)") (class "Default")
      (node (ref "U3") (pin "27") (pinfunction "GPIO03_27") (pintype "bidirectional"))
    )
    (net (code "84") (name "unconnected-(U3-GPIO04-Pad20)") (class "Default")
      (node (ref "U3") (pin "20") (pinfunction "GPIO04_20") (pintype "bidirectional"))
    )
    (net (code "85") (name "unconnected-(U3-GPIO12-Pad12)") (class "Default")
      (node (ref "U3") (pin "12") (pinfunction "GPIO12_12") (pintype "bidirectional"))
    )
    (net (code "86") (name "unconnected-(U3-GPIO15-Pad18)") (class "Default")
      (node (ref "U3") (pin "18") (pinfunction "GPIO15_18") (pintype "bidirectional"))
    )
    (net (code "87") (name "unconnected-(U3-GPIO32-Pad6)") (class "Default")
      (node (ref "U3") (pin "6") (pinfunction "GPIO32_6") (pintype "bidirectional"))
    )
    (net (code "88") (name "unconnected-(U3-GPIO33-Pad7)") (class "Default")
      (node (ref "U3") (pin "7") (pinfunction "GPIO33_7") (pintype "bidirectional"))
    )
    (net (code "89") (name "unconnected-(U5-PadAI1)") (class "Default")
      (node (ref "U5") (pin "AI1") (pinfunction "AI1_AI1") (pintype "bidirectional"))
    )
    (net (code "90") (name "unconnected-(U5-PadAI2)") (class "Default")
      (node (ref "U5") (pin "AI2") (pinfunction "AI2_AI2") (pintype "bidirectional"))
    )
    (net (code "91") (name "unconnected-(U5-PadGI1)") (class "Default")
      (node (ref "U5") (pin "GI1") (pinfunction "GI1_GI1") (pintype "bidirectional"))
    )
    (net (code "92") (name "unconnected-(U5-PadGI2)") (class "Default")
      (node (ref "U5") (pin "GI2") (pinfunction "GI2_GI2") (pintype "bidirectional"))
    )
    (net (code "93") (name "unconnected-(U5-PadRST)") (class "Default")
      (node (ref "U5") (pin "RST") (pinfunction "RST_RST") (pintype "bidirectional"))
    )
  )
)
